# Buck.net
KiCad netlist of a schematic drawn in Altium Designer
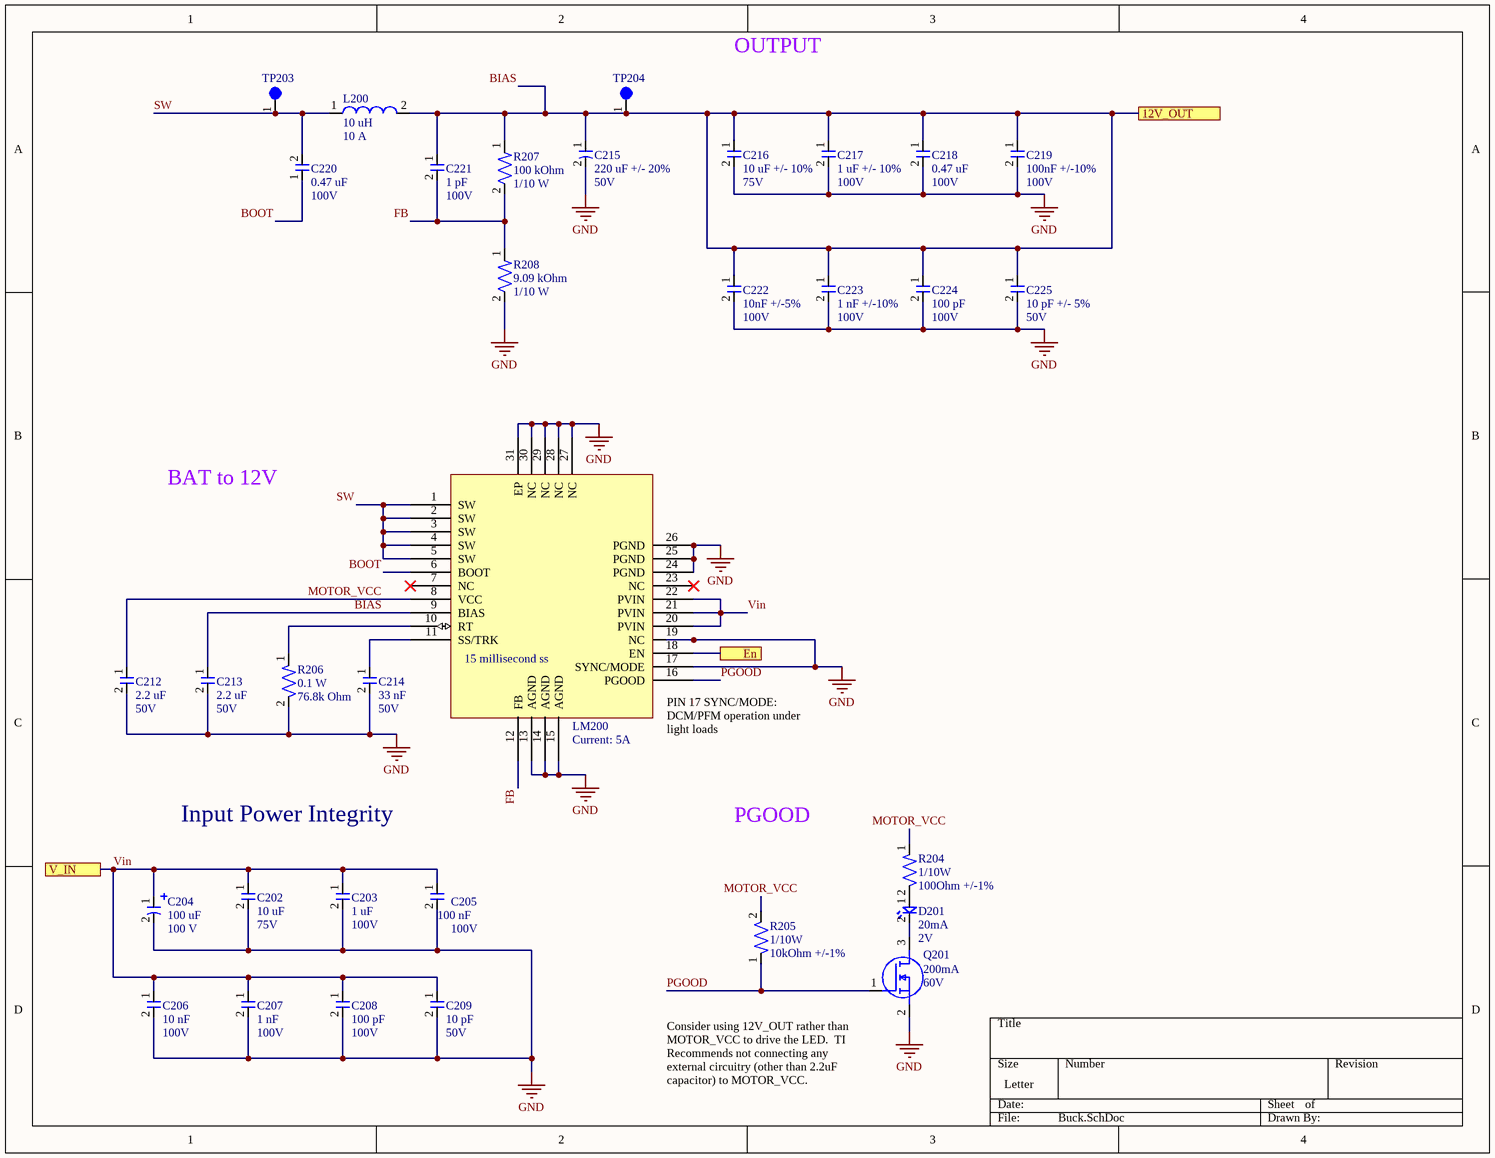
[diagram p0: Buck.SchDoc]

(export (version "E")
  (design (tool "Eeschema 10.0.6"))
  (components
    (comp (ref "C202")
      (value "C3225X7R1N106K250AC")
      (footprint "MasterLib:CAP-1210")
      (description "10 µF ±10% 75V Ceramic Capacitor X7R 1210 (3225 Metric)")
      (fields
        (field (name "CAPACITANCE") "10 uF")
        (field (name "VOLTAGE RATING") "75V")
        (field (name "TOLERANCE") "10%")
      )
      (libsource (lib "MasterLib") (part "CAP-10U-0004"))
    )
    (comp (ref "C203")
      (value "CL31B105KCHNNNE")
      (footprint "MasterLib:CAP-1206")
      (description "1 µF ±10% 100V Ceramic Capacitor X7R 1206 (3216 Metric)")
      (fields
        (field (name "CAPACITANCE") "1 uF")
        (field (name "VOLTAGE") "100V")
        (field (name "TOLERANCE") "10%")
      )
      (libsource (lib "MasterLib") (part "CAP-1U-0001"))
    )
    (comp (ref "C204")
      (value "100SEV100M12.5X16")
      (footprint "MasterLib:ELEC-100U-0001")
      (description "100 µF 100 V Aluminum Electrolytic Capacitors Radial, Can - SMD 2000 Hrs @ 85°C")
      (fields
        (field (name "MANUFACTURER") "Rubycon")
        (field (name "TOLERANCE") "20%")
        (field (name "CAPACITANCE") "100 uF")
        (field (name "VOLTAGE") "100 V")
      )
      (libsource (lib "MasterLib") (part "ELEC-100U-0001"))
    )
    (comp (ref "C205")
      (value "CC0603KRX7R0BB104")
      (footprint "MasterLib:CAP-0603")
      (description "CAP CER 0.1UF 100V X7R 0603")
      (fields
        (field (name "MANUFACTURER") "YAGEO")
        (field (name "CAPACITANCE") "100 nF")
        (field (name "VOLTAGE RATING") "100V")
        (field (name "TOLERANCE") "10%")
      )
      (libsource (lib "MasterLib") (part "CAP-100N-0001"))
    )
    (comp (ref "C206")
      (value "C1608C0G2A103J080AC")
      (footprint "MasterLib:CAP-0603")
      (description "CAP CER 10000PF 100V C0G 0603")
      (fields
        (field (name "MANUFACTURER") "TDK Corporation")
        (field (name "CAPACITANCE") "10 nF")
        (field (name "VOLTAGE RATING") "100V")
        (field (name "TOLERANCE") "5%")
      )
      (libsource (lib "MasterLib") (part "CAP-10N-0002"))
    )
    (comp (ref "C207")
      (value "C0603Y102K1RAC7867")
      (footprint "MasterLib:CAP-0603")
      (description "1000 pF ±10% 100V Ceramic Capacitor X7R 0603 (1608 Metric)")
      (fields
        (field (name "CAPACITANCE") "1 nF")
        (field (name "VOLTAGE") "100V")
        (field (name "TOLERANCE") "10%")
      )
      (libsource (lib "MasterLib") (part "CAP-1N-0001"))
    )
    (comp (ref "C208")
      (value "0603N101J101CT")
      (footprint "MasterLib:CAP-0603")
      (description "100 pF ±5% 100V Ceramic Capacitor C0G, NP0 0603 (1608 Metric)")
      (fields
        (field (name "TOLERANCE") "5%")
        (field (name "CAPACITANCE") "100 pF")
        (field (name "VOLTAGE") "100V")
      )
      (libsource (lib "MasterLib") (part "CAP-100P-0002"))
    )
    (comp (ref "C209")
      (value "0603N100J500CT")
      (footprint "MasterLib:CAP-0603")
      (description "10 pF ±5% 50V Ceramic Capacitor C0G, NP0 0603 (1608 Metric)")
      (fields
        (field (name "MANUFACTURER") "Walshin Technology Corporation")
        (field (name "CAPACITANCE") "10 pF")
        (field (name "VOLTAGE RATING") "50V")
        (field (name "TOLERANCE") "5%")
      )
      (libsource (lib "MasterLib") (part "CAP-10P-0001"))
    )
    (comp (ref "C212")
      (value "UMK107BBJ225KA-T")
      (footprint "MasterLib:CAP-0603")
      (description "2.2 µF ±10% 50V Ceramic Capacitor X5R 0603 (1608 Metric)")
      (fields
        (field (name "CAPACITANCE") "2.2 uF")
        (field (name "OLTAGE") "50V")
        (field (name "TOLERANCE") "10%")
      )
      (libsource (lib "MasterLib") (part "CAP-2.2U-0001"))
    )
    (comp (ref "C213")
      (value "UMK107BBJ225KA-T")
      (footprint "MasterLib:CAP-0603")
      (description "2.2 µF ±10% 50V Ceramic Capacitor X5R 0603 (1608 Metric)")
      (fields
        (field (name "CAPACITANCE") "2.2 uF")
        (field (name "OLTAGE") "50V")
        (field (name "TOLERANCE") "10%")
      )
      (libsource (lib "MasterLib") (part "CAP-2.2U-0001"))
    )
    (comp (ref "C214")
      (value "CC0603KRX7R9BB333")
      (footprint "MasterLib:CAP-0603")
      (description "0.033 µF ±10% 50V Ceramic Capacitor X7R 0603 (1608 Metric)")
      (fields
        (field (name "MANUFACTURER") "YAGEO")
        (field (name "CAPACITANCE") "33 nF")
        (field (name "VOLTAGE RATING") "50V")
        (field (name "TOLERANCE") "10%")
      )
      (libsource (lib "MasterLib") (part "CAP-33N-0001"))
    )
    (comp (ref "C215")
      (value "50TZV220M10X10.5")
      (footprint "MasterLib:ELEC-220U-0003")
      (description "220 µF 50 V Aluminum Electrolytic Capacitors Radial, Can - SMD 2000 Hrs @ 105°C")
      (fields (field (name "CAPACITANCE") "220 uF +/- 20%") (field (name "VOLTAGE RATING") "50V"))
      (libsource (lib "MasterLib") (part "ELEC-220U-0003"))
    )
    (comp (ref "C216")
      (value "C3225X7R1N106K250AC")
      (footprint "MasterLib:CAP-1210")
      (description "10 µF ±10% 75V Ceramic Capacitor X7R 1210 (3225 Metric)")
      (fields (field (name "CAPACITANCE") "10 uF +/- 10%") (field (name "VOLTAGE RATING") "75V"))
      (libsource (lib "MasterLib") (part "CAP-10U-0004"))
    )
    (comp (ref "C217")
      (value "CL31B105KCHNNNE")
      (footprint "MasterLib:CAP-1206")
      (description "1 µF ±10% 100V Ceramic Capacitor X7R 1206 (3216 Metric)")
      (fields (field (name "CAPACITANCE") "1 uF +/- 10%") (field (name "VOLTAGE") "100V"))
      (libsource (lib "MasterLib") (part "CAP-1U-0001"))
    )
    (comp (ref "C218")
      (value "KAM21KR72A474KL")
      (footprint "MasterLib:CAP-0805")
      (description "0.47 µF ±10% 100V Ceramic Capacitor X7R 0805 (2012 Metric)")
      (fields
        (field (name "TOLERANCE") "+/- 10%")
        (field (name "CAPACITANCE") "0.47 uF")
        (field (name "VOLTAGE") "100V")
      )
      (libsource (lib "MasterLib") (part "CAP-0.47U-0001"))
    )
    (comp (ref "C219")
      (value "CC0603KRX7R0BB104")
      (footprint "MasterLib:CAP-0603")
      (description "CAP CER 0.1UF 100V X7R 0603")
      (fields
        (field (name "MANUFACTURER") "YAGEO")
        (field (name "CAPACITANCE") "100nF +/-10%")
        (field (name "VOLTAGE RATING") "100V")
      )
      (libsource (lib "MasterLib") (part "CAP-100N-0001"))
    )
    (comp (ref "C220")
      (value "KAM21KR72A474KL")
      (footprint "MasterLib:CAP-0805")
      (description "0.47 µF ±10% 100V Ceramic Capacitor X7R 0805 (2012 Metric)")
      (fields
        (field (name "TOLERANCE") "+/- 10%")
        (field (name "CAPACITANCE") "0.47 uF")
        (field (name "VOLTAGE") "100V")
      )
      (libsource (lib "MasterLib") (part "CAP-0.47U-0001"))
    )
    (comp (ref "C221")
      (value "885012006087")
      (footprint "MasterLib:CAP-0603")
      (description "1 pF ±0.25pF 100V Ceramic Capacitor C0G, NP0 0603 (1608 Metric)")
      (fields
        (field (name "TOLERANCE") "+/- 0.25 pF")
        (field (name "CAPACITANCE") "1 pF")
        (field (name "VOLTAGE") "100V")
      )
      (libsource (lib "MasterLib") (part "CAP-1P-0001"))
    )
    (comp (ref "C222")
      (value "C1608C0G2A103J080AC")
      (footprint "MasterLib:CAP-0603")
      (description "CAP CER 10000PF 100V C0G 0603")
      (fields
        (field (name "MANUFACTURER") "TDK Corporation")
        (field (name "CAPACITANCE") "10nF +/-5%")
        (field (name "VOLTAGE RATING") "100V")
      )
      (libsource (lib "MasterLib") (part "CAP-10N-0002"))
    )
    (comp (ref "C223")
      (value "C0603Y102K1RAC7867")
      (footprint "MasterLib:CAP-0603")
      (description "1000 pF ±10% 100V Ceramic Capacitor X7R 0603 (1608 Metric)")
      (fields (field (name "CAPACITANCE") "1 nF +/-10%") (field (name "VOLTAGE") "100V"))
      (libsource (lib "MasterLib") (part "CAP-1N-0001"))
    )
    (comp (ref "C224")
      (value "0603N101J101CT")
      (footprint "MasterLib:CAP-0603")
      (description "100 pF ±5% 100V Ceramic Capacitor C0G, NP0 0603 (1608 Metric)")
      (fields
        (field (name "TOLERANCE") "+/-5%")
        (field (name "CAPACITANCE") "100 pF")
        (field (name "VOLTAGE") "100V")
      )
      (libsource (lib "MasterLib") (part "CAP-100P-0002"))
    )
    (comp (ref "C225")
      (value "0603N100J500CT")
      (footprint "MasterLib:CAP-0603")
      (description "10 pF ±5% 50V Ceramic Capacitor C0G, NP0 0603 (1608 Metric)")
      (fields
        (field (name "MANUFACTURER") "Walshin Technology Corporation")
        (field (name "CAPACITANCE") "10 pF +/- 5%")
        (field (name "VOLTAGE RATING") "50V")
      )
      (libsource (lib "MasterLib") (part "CAP-10P-0001"))
    )
    (comp (ref "D201")
      (value "150060AS75000")
      (footprint "MasterLib:LED-0603")
      (description "Amber LED 0603")
      (fields
        (field (name "MANUFACTURER") "Wurth Electronik")
        (field (name "CURRENT RATING") "20mA")
        (field (name "VF") "2V")
      )
      (libsource (lib "MasterLib") (part "LED_Amber_0001"))
    )
    (comp (ref "L200")
      (value "SRP1270-100M")
      (footprint "MasterLib:PWRIND-10U-0002")
      (description "10 µH Shielded Drum Core, Wirewound Inductor 10 A 16.8mOhm Max Nonstandard")
      (fields
        (field (name "TOLERANCE") "+/- 20%")
        (field (name "INDUCTANCE") "10 uH")
        (field (name "DCI") "10 A")
      )
      (libsource (lib "MasterLib") (part "PWRIND-10U-0002"))
    )
    (comp (ref "LM200")
      (value "LM76005RNPR")
      (footprint "IC-30-WQFN(6x4)")
      (description "Buck Switching Regulator IC Positive Adjustable 1V 1 Output 5A 30-WFQFN Exposed Pad")
      (fields (field (name "MANUFACTURER") "Texas Instruments") (field (name "CURRENT") "5A"))
      (libsource (lib "MasterLib") (part "IC-BUCK-0006"))
    )
    (comp (ref "Q201")
      (value "T2N7002AK,LM")
      (footprint "MasterLib:NMOS-SOT23-3")
      (description "MOSFET N-CH 60V 200MA SOT23")
      (fields
        (field (name "MANUFACTURER") "Toshiba")
        (field (name "ID-CONTINUOUS") "200mA")
        (field (name "VDS-MAX") "60V")
      )
      (libsource (lib "MasterLib") (part "NMOS-200MA-0001"))
    )
    (comp (ref "R204")
      (value "AC0603FR-10100RL")
      (footprint "MasterLib:RES-0603")
      (description "100 Ohms ±1% 0.1W, 1/10W Chip Resistor 0603 (1608 Metric) Automotive AEC-Q200 Thick Film")
      (fields
        (field (name "MANUFACTURER") "YAGEO")
        (field (name "POWER RATING") "1/10W")
        (field (name "RESISTANCE") "100Ohm +/-1%")
      )
      (libsource (lib "MasterLib") (part "RES-100-0002"))
    )
    (comp (ref "R205")
      (value "RC0603FR-0710KP")
      (footprint "MasterLib:RES-0603")
      (description "RES SMD 10K OHM 1% 1/10W 0603")
      (fields
        (field (name "MANUFACTURER") "YAGEO")
        (field (name "POWER RATING") "1/10W")
        (field (name "RESISTANCE") "10kOhm +/-1%")
      )
      (libsource (lib "MasterLib") (part "RES-10K-0002"))
    )
    (comp (ref "R206")
      (value "RC0603FR-0776K8L")
      (footprint "MasterLib:RES-0603")
      (description "76.8 kOhms ±1% 0.1W, 1/10W Chip Resistor 0603 (1608 Metric) Moisture Resistant Thick Film")
      (fields
        (field (name "MANUFACTURER") "Yageo")
        (field (name "TOLERANCE") "1%")
        (field (name "POWER") "0.1 W")
        (field (name "RESISTANCE") "76.8k Ohm")
      )
      (libsource (lib "MasterLib") (part "RES-76.8K-0001"))
    )
    (comp (ref "R207")
      (value "RC0603FR-07100KL")
      (footprint "MasterLib:RES-0603")
      (description "100 kOhms ±1% 0.1W, 1/10W Chip Resistor 0603 (1608 Metric) Moisture Resistant Thick Film")
      (fields
        (field (name "TOLERANCE") "+/- 1%")
        (field (name "RESISTANCE") "100 kOhm")
        (field (name "POWER") "1/10 W")
      )
      (libsource (lib "MasterLib") (part "RES-100K-0003"))
    )
    (comp (ref "R208")
      (value "RC0603FR-079K09L")
      (footprint "MasterLib:RES-0603")
      (description "9.09 kOhms ±1% 0.1W, 1/10W Chip Resistor 0603 (1608 Metric) Moisture Resistant Thick Film")
      (fields
        (field (name "TOLERANCE") "+/-1%")
        (field (name "RESISTANCE") "9.09 kOhm")
        (field (name "POWER") "1/10 W")
      )
      (libsource (lib "MasterLib") (part "RES-9.09K-0001"))
    )
    (comp (ref "TP203")
      (value "5003")
      (footprint "MasterLib:TEST-POINT-0001")
      (description "Oranange PC Test Point, Miniature Phoisphor Bronze Silver Plating Through Hole Mounting Type")
      (libsource (lib "MasterLib") (part "TEST-POINT-0001"))
    )
    (comp (ref "TP204")
      (value "5003")
      (footprint "MasterLib:TEST-POINT-0001")
      (description "Oranange PC Test Point, Miniature Phoisphor Bronze Silver Plating Through Hole Mounting Type")
      (libsource (lib "MasterLib") (part "TEST-POINT-0001"))
    )
  )
  (nets
    (net (code "1") (name "/BIAS") (class "Default")
      (node (ref "C213") (pin "1") (pinfunction "1_1") (pintype "passive"))
      (node (ref "C215") (pin "1") (pinfunction "1_1") (pintype "passive"))
      (node (ref "C216") (pin "1") (pinfunction "1_1") (pintype "passive"))
      (node (ref "C217") (pin "1") (pinfunction "1_1") (pintype "passive"))
      (node (ref "C218") (pin "1") (pinfunction "1_1") (pintype "passive"))
      (node (ref "C219") (pin "1") (pinfunction "1_1") (pintype "passive"))
      (node (ref "C221") (pin "1") (pinfunction "1_1") (pintype "passive"))
      (node (ref "C222") (pin "1") (pinfunction "1_1") (pintype "passive"))
      (node (ref "C223") (pin "1") (pinfunction "1_1") (pintype "passive"))
      (node (ref "C224") (pin "1") (pinfunction "1_1") (pintype "passive"))
      (node (ref "C225") (pin "1") (pinfunction "1_1") (pintype "passive"))
      (node (ref "L200") (pin "2") (pinfunction "2_2") (pintype "passive"))
      (node (ref "LM200") (pin "9") (pinfunction "BIAS_9") (pintype "power_in"))
      (node (ref "R207") (pin "1") (pinfunction "1_1") (pintype "passive"))
      (node (ref "TP204") (pin "1") (pinfunction "0_1") (pintype "passive"))
    )
    (net (code "2") (name "/BOOT") (class "Default")
      (node (ref "C220") (pin "1") (pinfunction "1_1") (pintype "passive"))
      (node (ref "LM200") (pin "6") (pinfunction "BOOT_6") (pintype "power_in"))
    )
    (net (code "3") (name "/En") (class "Default")
      (node (ref "LM200") (pin "18") (pinfunction "EN_18") (pintype "power_in"))
    )
    (net (code "4") (name "/FB") (class "Default")
      (node (ref "C221") (pin "2") (pinfunction "2_2") (pintype "passive"))
      (node (ref "LM200") (pin "12") (pinfunction "FB_12") (pintype "power_in"))
      (node (ref "R207") (pin "2") (pinfunction "2_2") (pintype "passive"))
      (node (ref "R208") (pin "1") (pinfunction "1_1") (pintype "passive"))
    )
    (net (code "5") (name "/MOTOR_VCC") (class "Default")
      (node (ref "C212") (pin "1") (pinfunction "1_1") (pintype "passive"))
      (node (ref "LM200") (pin "8") (pinfunction "VCC_8") (pintype "power_in"))
      (node (ref "R204") (pin "1") (pinfunction "1_1") (pintype "passive"))
      (node (ref "R205") (pin "2") (pinfunction "2_2") (pintype "passive"))
    )
    (net (code "6") (name "/PGOOD") (class "Default")
      (node (ref "LM200") (pin "16") (pinfunction "PGOOD_16") (pintype "power_in"))
      (node (ref "Q201") (pin "1") (pinfunction "G_1") (pintype "passive"))
      (node (ref "R205") (pin "1") (pinfunction "1_1") (pintype "passive"))
    )
    (net (code "7") (name "/SW") (class "Default")
      (node (ref "C220") (pin "2") (pinfunction "2_2") (pintype "passive"))
      (node (ref "L200") (pin "1") (pinfunction "1_1") (pintype "passive"))
      (node (ref "LM200") (pin "1") (pinfunction "SW_1") (pintype "power_in"))
      (node (ref "LM200") (pin "2") (pinfunction "SW_2") (pintype "power_in"))
      (node (ref "LM200") (pin "3") (pinfunction "SW_3") (pintype "power_in"))
      (node (ref "LM200") (pin "4") (pinfunction "SW_4") (pintype "power_in"))
      (node (ref "LM200") (pin "5") (pinfunction "SW_5") (pintype "power_in"))
      (node (ref "TP203") (pin "1") (pinfunction "0_1") (pintype "passive"))
    )
    (net (code "8") (name "/Vin") (class "Default")
      (node (ref "C202") (pin "1") (pinfunction "1_1") (pintype "passive"))
      (node (ref "C203") (pin "1") (pinfunction "1_1") (pintype "passive"))
      (node (ref "C204") (pin "1") (pinfunction "1_1") (pintype "passive"))
      (node (ref "C205") (pin "1") (pinfunction "1_1") (pintype "passive"))
      (node (ref "C206") (pin "1") (pinfunction "1_1") (pintype "passive"))
      (node (ref "C207") (pin "1") (pinfunction "1_1") (pintype "passive"))
      (node (ref "C208") (pin "1") (pinfunction "1_1") (pintype "passive"))
      (node (ref "C209") (pin "1") (pinfunction "1_1") (pintype "passive"))
      (node (ref "LM200") (pin "20") (pinfunction "PVIN_20") (pintype "power_in"))
      (node (ref "LM200") (pin "21") (pinfunction "PVIN_21") (pintype "power_in"))
      (node (ref "LM200") (pin "22") (pinfunction "PVIN_22") (pintype "power_in"))
    )
    (net (code "9") (name "GND") (class "Default")
      (node (ref "C202") (pin "2") (pinfunction "2_2") (pintype "passive"))
      (node (ref "C203") (pin "2") (pinfunction "2_2") (pintype "passive"))
      (node (ref "C204") (pin "2") (pinfunction "2_2") (pintype "passive"))
      (node (ref "C205") (pin "2") (pinfunction "2_2") (pintype "passive"))
      (node (ref "C206") (pin "2") (pinfunction "2_2") (pintype "passive"))
      (node (ref "C207") (pin "2") (pinfunction "2_2") (pintype "passive"))
      (node (ref "C208") (pin "2") (pinfunction "2_2") (pintype "passive"))
      (node (ref "C209") (pin "2") (pinfunction "2_2") (pintype "passive"))
      (node (ref "C212") (pin "2") (pinfunction "2_2") (pintype "passive"))
      (node (ref "C213") (pin "2") (pinfunction "2_2") (pintype "passive"))
      (node (ref "C214") (pin "2") (pinfunction "2_2") (pintype "passive"))
      (node (ref "C215") (pin "2") (pinfunction "2_2") (pintype "passive"))
      (node (ref "C216") (pin "2") (pinfunction "2_2") (pintype "passive"))
      (node (ref "C217") (pin "2") (pinfunction "2_2") (pintype "passive"))
      (node (ref "C218") (pin "2") (pinfunction "2_2") (pintype "passive"))
      (node (ref "C219") (pin "2") (pinfunction "2_2") (pintype "passive"))
      (node (ref "C222") (pin "2") (pinfunction "2_2") (pintype "passive"))
      (node (ref "C223") (pin "2") (pinfunction "2_2") (pintype "passive"))
      (node (ref "C224") (pin "2") (pinfunction "2_2") (pintype "passive"))
      (node (ref "C225") (pin "2") (pinfunction "2_2") (pintype "passive"))
      (node (ref "LM200") (pin "13") (pinfunction "AGND_13") (pintype "power_in"))
      (node (ref "LM200") (pin "14") (pinfunction "AGND_14") (pintype "power_in"))
      (node (ref "LM200") (pin "15") (pinfunction "AGND_15") (pintype "power_in"))
      (node (ref "LM200") (pin "17") (pinfunction "SYNC/MODE_17") (pintype "power_in"))
      (node (ref "LM200") (pin "19") (pinfunction "NC_19") (pintype "power_in"))
      (node (ref "LM200") (pin "24") (pinfunction "PGND_24") (pintype "power_in"))
      (node (ref "LM200") (pin "25") (pinfunction "PGND_25") (pintype "power_in"))
      (node (ref "LM200") (pin "26") (pinfunction "PGND_26") (pintype "power_in"))
      (node (ref "LM200") (pin "27") (pinfunction "NC_27") (pintype "power_in"))
      (node (ref "LM200") (pin "28") (pinfunction "NC_28") (pintype "power_in"))
      (node (ref "LM200") (pin "29") (pinfunction "NC_29") (pintype "power_in"))
      (node (ref "LM200") (pin "30") (pinfunction "NC_30") (pintype "power_in"))
      (node (ref "LM200") (pin "31") (pinfunction "EP_31") (pintype "power_in"))
      (node (ref "Q201") (pin "2") (pinfunction "S_2") (pintype "passive"))
      (node (ref "R206") (pin "2") (pinfunction "2_2") (pintype "passive"))
      (node (ref "R208") (pin "2") (pinfunction "2_2") (pintype "passive"))
    )
    (net (code "10") (name "Net-(D201-Pad1)") (class "Default")
      (node (ref "D201") (pin "1") (pinfunction "1_1") (pintype "passive"))
      (node (ref "R204") (pin "2") (pinfunction "2_2") (pintype "passive"))
    )
    (net (code "11") (name "Net-(LM200-RT)") (class "Default")
      (node (ref "LM200") (pin "10") (pinfunction "RT_10") (pintype "bidirectional"))
      (node (ref "R206") (pin "1") (pinfunction "1_1") (pintype "passive"))
    )
    (net (code "12") (name "Net-(LM200-SS{slash}TRK)") (class "Default")
      (node (ref "C214") (pin "1") (pinfunction "1_1") (pintype "passive"))
      (node (ref "LM200") (pin "11") (pinfunction "SS/TRK_11") (pintype "passive"))
    )
    (net (code "13") (name "Net-(Q201-D)") (class "Default")
      (node (ref "D201") (pin "2") (pinfunction "2_2") (pintype "passive"))
      (node (ref "Q201") (pin "3") (pinfunction "D_3") (pintype "passive"))
    )
    (net (code "14") (name "unconnected-(LM200-NC-Pad7)") (class "Default")
      (node (ref "LM200") (pin "7") (pinfunction "NC_7") (pintype "power_in+no_connect"))
    )
    (net (code "15") (name "unconnected-(LM200-NC-Pad23)") (class "Default")
      (node (ref "LM200") (pin "23") (pinfunction "NC_23") (pintype "tri_state+no_connect"))
    )
  )
)
